# duinolpcfwhspi.net
KiCad netlist of a schematic drawn in EAGLE
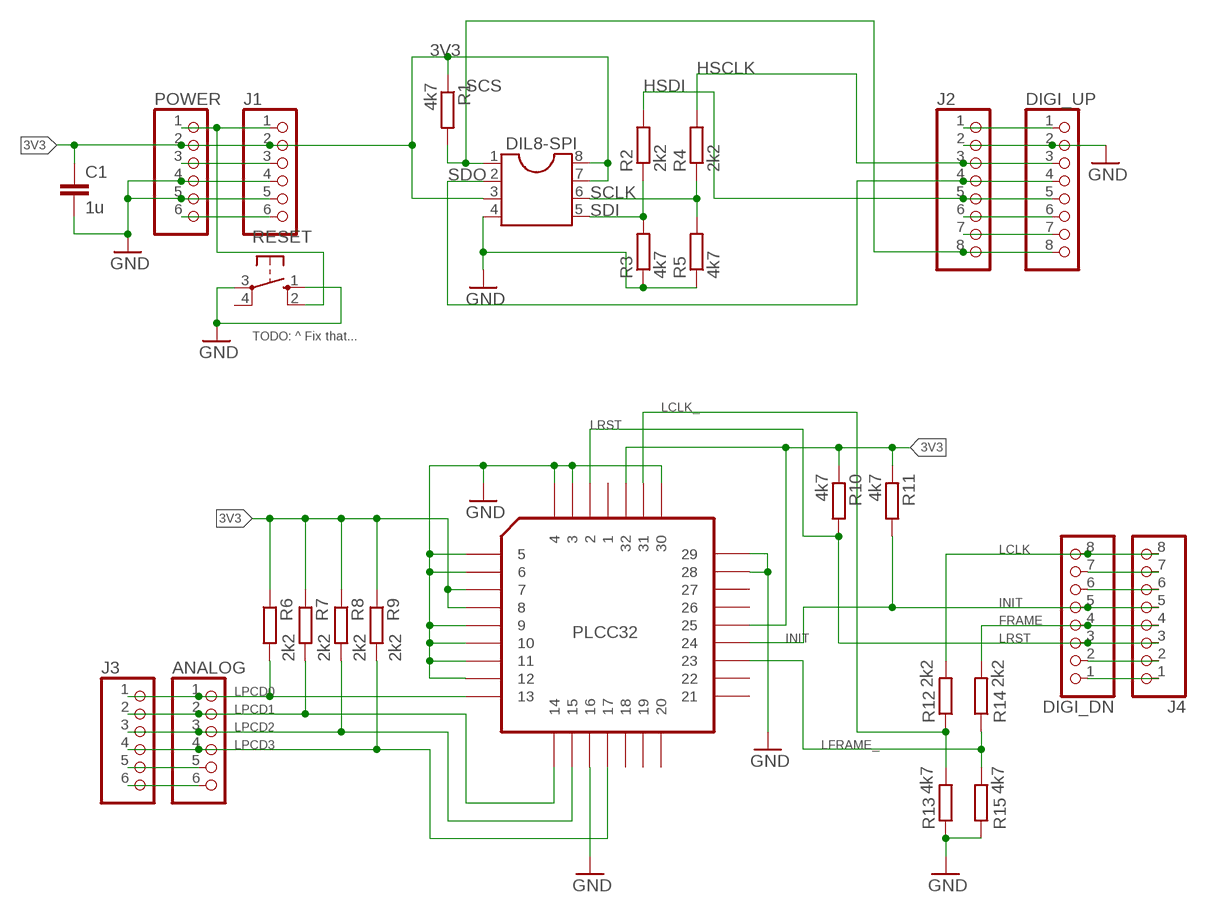
[diagram p0: schematic, sheet 1]

(export (version "E")
  (design (tool "Eeschema 10.0.6"))
  (components
    (comp (ref "ANALOG")
      (value "PINHD-1X6")
      (footprint "eagle-import:1X06")
      (libsource (lib "eagle-import") (part "PINHD-1X6"))
    )
    (comp (ref "C1")
      (value "1u")
      (footprint "eagle-import:C025-025X050")
      (libsource (lib "eagle-import") (part "C-EU025-025X050"))
    )
    (comp (ref "DIGI_DN")
      (value "PINHD-1X8TH")
      (footprint "eagle-import:1X08-TH")
      (libsource (lib "eagle-import") (part "PINHD-1X8TH"))
    )
    (comp (ref "DIGI_UP")
      (value "PINHD-1X8TH")
      (footprint "eagle-import:1X08-TH")
      (libsource (lib "eagle-import") (part "PINHD-1X8TH"))
    )
    (comp (ref "DIL8-SPI")
      (value "DIL8")
      (footprint "eagle-import:DIL08")
      (libsource (lib "eagle-import") (part "DIL8"))
    )
    (comp (ref "J1")
      (value "PINHD-1X6")
      (footprint "eagle-import:1X06")
      (libsource (lib "eagle-import") (part "PINHD-1X6"))
    )
    (comp (ref "J2")
      (value "PINHD-1X8TH")
      (footprint "eagle-import:1X08-TH")
      (libsource (lib "eagle-import") (part "PINHD-1X8TH"))
    )
    (comp (ref "J3")
      (value "PINHD-1X6")
      (footprint "eagle-import:1X06")
      (libsource (lib "eagle-import") (part "PINHD-1X6"))
    )
    (comp (ref "J4")
      (value "PINHD-1X8TH")
      (footprint "eagle-import:1X08-TH")
      (libsource (lib "eagle-import") (part "PINHD-1X8TH"))
    )
    (comp (ref "PLCC32")
      (value "PLCC32")
      (footprint "eagle-import:PLCC-S32")
      (libsource (lib "eagle-import") (part "PLCC32"))
    )
    (comp (ref "POWER")
      (value "PINHD-1X6")
      (footprint "eagle-import:1X06")
      (libsource (lib "eagle-import") (part "PINHD-1X6"))
    )
    (comp (ref "R1")
      (value "4k7")
      (footprint "eagle-import:0207_2V")
      (libsource (lib "eagle-import") (part "R-EU_0207/2V"))
    )
    (comp (ref "R2")
      (value "2k2")
      (footprint "eagle-import:0207_2V")
      (libsource (lib "eagle-import") (part "R-EU_0207/2V"))
    )
    (comp (ref "R3")
      (value "4k7")
      (footprint "eagle-import:0207_2V")
      (libsource (lib "eagle-import") (part "R-EU_0207/2V"))
    )
    (comp (ref "R4")
      (value "2k2")
      (footprint "eagle-import:0207_2V")
      (libsource (lib "eagle-import") (part "R-EU_0207/2V"))
    )
    (comp (ref "R5")
      (value "4k7")
      (footprint "eagle-import:0207_2V")
      (libsource (lib "eagle-import") (part "R-EU_0207/2V"))
    )
    (comp (ref "R6")
      (value "2k2")
      (footprint "eagle-import:0207_2V")
      (libsource (lib "eagle-import") (part "R-EU_0207/2V"))
    )
    (comp (ref "R7")
      (value "2k2")
      (footprint "eagle-import:0207_2V")
      (libsource (lib "eagle-import") (part "R-EU_0207/2V"))
    )
    (comp (ref "R8")
      (value "2k2")
      (footprint "eagle-import:0207_2V")
      (libsource (lib "eagle-import") (part "R-EU_0207/2V"))
    )
    (comp (ref "R9")
      (value "2k2")
      (footprint "eagle-import:0207_2V")
      (libsource (lib "eagle-import") (part "R-EU_0207/2V"))
    )
    (comp (ref "R10")
      (value "4k7")
      (footprint "eagle-import:0207_2V")
      (libsource (lib "eagle-import") (part "R-EU_0207/2V"))
    )
    (comp (ref "R11")
      (value "4k7")
      (footprint "eagle-import:0207_2V")
      (libsource (lib "eagle-import") (part "R-EU_0207/2V"))
    )
    (comp (ref "R12")
      (value "2k2")
      (footprint "eagle-import:0207_2V")
      (libsource (lib "eagle-import") (part "R-EU_0207/2V"))
    )
    (comp (ref "R13")
      (value "4k7")
      (footprint "eagle-import:0207_2V")
      (libsource (lib "eagle-import") (part "R-EU_0207/2V"))
    )
    (comp (ref "R14")
      (value "2k2")
      (footprint "eagle-import:0207_2V")
      (libsource (lib "eagle-import") (part "R-EU_0207/2V"))
    )
    (comp (ref "R15")
      (value "4k7")
      (footprint "eagle-import:0207_2V")
      (libsource (lib "eagle-import") (part "R-EU_0207/2V"))
    )
    (comp (ref "RESET")
      (value "10-XX")
      (footprint "eagle-import:B3F-10XX")
      (libsource (lib "eagle-import") (part "10-XX"))
    )
  )
  (nets
    (net (code "1") (name "/FRAME") (class "Default")
      (node (ref "DIGI_DN") (pin "4") (pinfunction "4_4") (pintype "passive"))
      (node (ref "J4") (pin "4") (pinfunction "4_4") (pintype "passive"))
      (node (ref "R14") (pin "2") (pinfunction "2_2") (pintype "passive"))
    )
    (net (code "2") (name "/HSCLK") (class "Default")
      (node (ref "DIGI_UP") (pin "3") (pinfunction "3_3") (pintype "passive"))
      (node (ref "J2") (pin "3") (pinfunction "3_3") (pintype "passive"))
      (node (ref "R4") (pin "2") (pinfunction "2_2") (pintype "passive"))
    )
    (net (code "3") (name "/HSDI") (class "Default")
      (node (ref "DIGI_UP") (pin "5") (pinfunction "5_5") (pintype "passive"))
      (node (ref "J2") (pin "5") (pinfunction "5_5") (pintype "passive"))
      (node (ref "R2") (pin "2") (pinfunction "2_2") (pintype "passive"))
    )
    (net (code "4") (name "/INIT") (class "Default")
      (node (ref "DIGI_DN") (pin "5") (pinfunction "5_5") (pintype "passive"))
      (node (ref "J4") (pin "5") (pinfunction "5_5") (pintype "passive"))
      (node (ref "PLCC32") (pin "24") (pinfunction "24_24") (pintype "passive"))
      (node (ref "R11") (pin "2") (pinfunction "2_2") (pintype "passive"))
    )
    (net (code "5") (name "/LCLK") (class "Default")
      (node (ref "DIGI_DN") (pin "8") (pinfunction "8_8") (pintype "passive"))
      (node (ref "J4") (pin "8") (pinfunction "8_8") (pintype "passive"))
      (node (ref "R12") (pin "2") (pinfunction "2_2") (pintype "passive"))
    )
    (net (code "6") (name "/LCLK_") (class "Default")
      (node (ref "PLCC32") (pin "31") (pinfunction "31_31") (pintype "passive"))
      (node (ref "R12") (pin "1") (pinfunction "1_1") (pintype "passive"))
      (node (ref "R13") (pin "2") (pinfunction "2_2") (pintype "passive"))
    )
    (net (code "7") (name "/LFRAME_") (class "Default")
      (node (ref "PLCC32") (pin "23") (pinfunction "23_23") (pintype "passive"))
      (node (ref "R14") (pin "1") (pinfunction "1_1") (pintype "passive"))
      (node (ref "R15") (pin "2") (pinfunction "2_2") (pintype "passive"))
    )
    (net (code "8") (name "/LPCD0") (class "Default")
      (node (ref "ANALOG") (pin "1") (pinfunction "1_1") (pintype "passive"))
      (node (ref "J3") (pin "1") (pinfunction "1_1") (pintype "passive"))
      (node (ref "PLCC32") (pin "13") (pinfunction "13_13") (pintype "passive"))
      (node (ref "R6") (pin "2") (pinfunction "2_2") (pintype "passive"))
    )
    (net (code "9") (name "/LPCD1") (class "Default")
      (node (ref "ANALOG") (pin "2") (pinfunction "2_2") (pintype "passive"))
      (node (ref "J3") (pin "2") (pinfunction "2_2") (pintype "passive"))
      (node (ref "PLCC32") (pin "14") (pinfunction "14_14") (pintype "passive"))
      (node (ref "R7") (pin "2") (pinfunction "2_2") (pintype "passive"))
    )
    (net (code "10") (name "/LPCD2") (class "Default")
      (node (ref "ANALOG") (pin "3") (pinfunction "3_3") (pintype "passive"))
      (node (ref "J3") (pin "3") (pinfunction "3_3") (pintype "passive"))
      (node (ref "PLCC32") (pin "15") (pinfunction "15_15") (pintype "passive"))
      (node (ref "R8") (pin "2") (pinfunction "2_2") (pintype "passive"))
    )
    (net (code "11") (name "/LPCD3") (class "Default")
      (node (ref "ANALOG") (pin "4") (pinfunction "4_4") (pintype "passive"))
      (node (ref "J3") (pin "4") (pinfunction "4_4") (pintype "passive"))
      (node (ref "PLCC32") (pin "17") (pinfunction "17_17") (pintype "passive"))
      (node (ref "R9") (pin "2") (pinfunction "2_2") (pintype "passive"))
    )
    (net (code "12") (name "/LRST") (class "Default")
      (node (ref "DIGI_DN") (pin "3") (pinfunction "3_3") (pintype "passive"))
      (node (ref "J4") (pin "3") (pinfunction "3_3") (pintype "passive"))
      (node (ref "PLCC32") (pin "2") (pinfunction "2_2") (pintype "passive"))
      (node (ref "R10") (pin "2") (pinfunction "2_2") (pintype "passive"))
    )
    (net (code "13") (name "/SCLK") (class "Default")
      (node (ref "DIL8-SPI") (pin "6") (pinfunction "6_6") (pintype "passive"))
      (node (ref "R4") (pin "1") (pinfunction "1_1") (pintype "passive"))
      (node (ref "R5") (pin "2") (pinfunction "2_2") (pintype "passive"))
    )
    (net (code "14") (name "/SCS") (class "Default")
      (node (ref "DIGI_UP") (pin "8") (pinfunction "8_8") (pintype "passive"))
      (node (ref "DIL8-SPI") (pin "1") (pinfunction "1_1") (pintype "passive"))
      (node (ref "J2") (pin "8") (pinfunction "8_8") (pintype "passive"))
      (node (ref "R1") (pin "2") (pinfunction "2_2") (pintype "passive"))
    )
    (net (code "15") (name "/SDI") (class "Default")
      (node (ref "DIL8-SPI") (pin "5") (pinfunction "5_5") (pintype "passive"))
      (node (ref "R2") (pin "1") (pinfunction "1_1") (pintype "passive"))
      (node (ref "R3") (pin "2") (pinfunction "2_2") (pintype "passive"))
    )
    (net (code "16") (name "/SDO") (class "Default")
      (node (ref "DIGI_UP") (pin "4") (pinfunction "4_4") (pintype "passive"))
      (node (ref "DIL8-SPI") (pin "2") (pinfunction "2_2") (pintype "passive"))
      (node (ref "J2") (pin "4") (pinfunction "4_4") (pintype "passive"))
    )
    (net (code "17") (name "3V3") (class "Default")
      (node (ref "C1") (pin "1") (pinfunction "1_1") (pintype "passive"))
      (node (ref "DIL8-SPI") (pin "3") (pinfunction "3_3") (pintype "passive"))
      (node (ref "DIL8-SPI") (pin "7") (pinfunction "7_7") (pintype "passive"))
      (node (ref "DIL8-SPI") (pin "8") (pinfunction "8_8") (pintype "passive"))
      (node (ref "J1") (pin "2") (pinfunction "2_2") (pintype "passive"))
      (node (ref "PLCC32") (pin "25") (pinfunction "25_25") (pintype "passive"))
      (node (ref "PLCC32") (pin "32") (pinfunction "32_32") (pintype "passive"))
      (node (ref "PLCC32") (pin "7") (pinfunction "7_7") (pintype "passive"))
      (node (ref "PLCC32") (pin "8") (pinfunction "8_8") (pintype "passive"))
      (node (ref "POWER") (pin "2") (pinfunction "2_2") (pintype "passive"))
      (node (ref "R1") (pin "1") (pinfunction "1_1") (pintype "passive"))
      (node (ref "R10") (pin "1") (pinfunction "1_1") (pintype "passive"))
      (node (ref "R11") (pin "1") (pinfunction "1_1") (pintype "passive"))
      (node (ref "R6") (pin "1") (pinfunction "1_1") (pintype "passive"))
      (node (ref "R7") (pin "1") (pinfunction "1_1") (pintype "passive"))
      (node (ref "R8") (pin "1") (pinfunction "1_1") (pintype "passive"))
      (node (ref "R9") (pin "1") (pinfunction "1_1") (pintype "passive"))
    )
    (net (code "18") (name "GND") (class "Default")
      (node (ref "C1") (pin "2") (pinfunction "2_2") (pintype "passive"))
      (node (ref "DIGI_UP") (pin "2") (pinfunction "2_2") (pintype "passive"))
      (node (ref "DIL8-SPI") (pin "4") (pinfunction "4_4") (pintype "passive"))
      (node (ref "J1") (pin "4") (pinfunction "4_4") (pintype "passive"))
      (node (ref "J1") (pin "5") (pinfunction "5_5") (pintype "passive"))
      (node (ref "J2") (pin "2") (pinfunction "2_2") (pintype "passive"))
      (node (ref "PLCC32") (pin "10") (pinfunction "10_10") (pintype "passive"))
      (node (ref "PLCC32") (pin "11") (pinfunction "11_11") (pintype "passive"))
      (node (ref "PLCC32") (pin "12") (pinfunction "12_12") (pintype "passive"))
      (node (ref "PLCC32") (pin "16") (pinfunction "16_16") (pintype "passive"))
      (node (ref "PLCC32") (pin "28") (pinfunction "28_28") (pintype "passive"))
      (node (ref "PLCC32") (pin "29") (pinfunction "29_29") (pintype "passive"))
      (node (ref "PLCC32") (pin "3") (pinfunction "3_3") (pintype "passive"))
      (node (ref "PLCC32") (pin "30") (pinfunction "30_30") (pintype "passive"))
      (node (ref "PLCC32") (pin "4") (pinfunction "4_4") (pintype "passive"))
      (node (ref "PLCC32") (pin "5") (pinfunction "5_5") (pintype "passive"))
      (node (ref "PLCC32") (pin "6") (pinfunction "6_6") (pintype "passive"))
      (node (ref "PLCC32") (pin "9") (pinfunction "9_9") (pintype "passive"))
      (node (ref "POWER") (pin "4") (pinfunction "4_4") (pintype "passive"))
      (node (ref "POWER") (pin "5") (pinfunction "5_5") (pintype "passive"))
      (node (ref "R13") (pin "1") (pinfunction "1_1") (pintype "passive"))
      (node (ref "R15") (pin "1") (pinfunction "1_1") (pintype "passive"))
      (node (ref "R3") (pin "1") (pinfunction "1_1") (pintype "passive"))
      (node (ref "R5") (pin "1") (pinfunction "1_1") (pintype "passive"))
      (node (ref "RESET") (pin "1") (pinfunction "S_1") (pintype "passive"))
      (node (ref "RESET") (pin "3") (pinfunction "P_3") (pintype "passive"))
    )
    (net (code "19") (name "Net-(ANALOG-Pad5)") (class "Default")
      (node (ref "ANALOG") (pin "5") (pinfunction "5_5") (pintype "passive"))
      (node (ref "J3") (pin "5") (pinfunction "5_5") (pintype "passive"))
    )
    (net (code "20") (name "Net-(ANALOG-Pad6)") (class "Default")
      (node (ref "ANALOG") (pin "6") (pinfunction "6_6") (pintype "passive"))
      (node (ref "J3") (pin "6") (pinfunction "6_6") (pintype "passive"))
    )
    (net (code "21") (name "Net-(DIGI_DN-Pad1)") (class "Default")
      (node (ref "DIGI_DN") (pin "1") (pinfunction "1_1") (pintype "passive"))
      (node (ref "J4") (pin "1") (pinfunction "1_1") (pintype "passive"))
    )
    (net (code "22") (name "Net-(DIGI_DN-Pad2)") (class "Default")
      (node (ref "DIGI_DN") (pin "2") (pinfunction "2_2") (pintype "passive"))
      (node (ref "J4") (pin "2") (pinfunction "2_2") (pintype "passive"))
    )
    (net (code "23") (name "Net-(DIGI_DN-Pad6)") (class "Default")
      (node (ref "DIGI_DN") (pin "6") (pinfunction "6_6") (pintype "passive"))
      (node (ref "J4") (pin "6") (pinfunction "6_6") (pintype "passive"))
    )
    (net (code "24") (name "Net-(DIGI_DN-Pad7)") (class "Default")
      (node (ref "DIGI_DN") (pin "7") (pinfunction "7_7") (pintype "passive"))
      (node (ref "J4") (pin "7") (pinfunction "7_7") (pintype "passive"))
    )
    (net (code "25") (name "Net-(DIGI_UP-Pad1)") (class "Default")
      (node (ref "DIGI_UP") (pin "1") (pinfunction "1_1") (pintype "passive"))
      (node (ref "J2") (pin "1") (pinfunction "1_1") (pintype "passive"))
    )
    (net (code "26") (name "Net-(DIGI_UP-Pad6)") (class "Default")
      (node (ref "DIGI_UP") (pin "6") (pinfunction "6_6") (pintype "passive"))
      (node (ref "J2") (pin "6") (pinfunction "6_6") (pintype "passive"))
    )
    (net (code "27") (name "Net-(DIGI_UP-Pad7)") (class "Default")
      (node (ref "DIGI_UP") (pin "7") (pinfunction "7_7") (pintype "passive"))
      (node (ref "J2") (pin "7") (pinfunction "7_7") (pintype "passive"))
    )
    (net (code "28") (name "Net-(J1-Pad3)") (class "Default")
      (node (ref "J1") (pin "3") (pinfunction "3_3") (pintype "passive"))
      (node (ref "POWER") (pin "3") (pinfunction "3_3") (pintype "passive"))
    )
    (net (code "29") (name "Net-(J1-Pad6)") (class "Default")
      (node (ref "J1") (pin "6") (pinfunction "6_6") (pintype "passive"))
      (node (ref "POWER") (pin "6") (pinfunction "6_6") (pintype "passive"))
    )
    (net (code "30") (name "Net-(RESET-S1)") (class "Default")
      (node (ref "J1") (pin "1") (pinfunction "1_1") (pintype "passive"))
      (node (ref "POWER") (pin "1") (pinfunction "1_1") (pintype "passive"))
      (node (ref "RESET") (pin "2") (pinfunction "S1_2") (pintype "passive"))
    )
    (net (code "31") (name "unconnected-(PLCC32-Pad1)") (class "Default")
      (node (ref "PLCC32") (pin "1") (pinfunction "1_1") (pintype "passive"))
    )
    (net (code "32") (name "unconnected-(PLCC32-Pad18)") (class "Default")
      (node (ref "PLCC32") (pin "18") (pinfunction "18_18") (pintype "passive"))
    )
    (net (code "33") (name "unconnected-(PLCC32-Pad19)") (class "Default")
      (node (ref "PLCC32") (pin "19") (pinfunction "19_19") (pintype "passive"))
    )
    (net (code "34") (name "unconnected-(PLCC32-Pad20)") (class "Default")
      (node (ref "PLCC32") (pin "20") (pinfunction "20_20") (pintype "passive"))
    )
    (net (code "35") (name "unconnected-(PLCC32-Pad21)") (class "Default")
      (node (ref "PLCC32") (pin "21") (pinfunction "21_21") (pintype "passive"))
    )
    (net (code "36") (name "unconnected-(PLCC32-Pad22)") (class "Default")
      (node (ref "PLCC32") (pin "22") (pinfunction "22_22") (pintype "passive"))
    )
    (net (code "37") (name "unconnected-(PLCC32-Pad26)") (class "Default")
      (node (ref "PLCC32") (pin "26") (pinfunction "26_26") (pintype "passive"))
    )
    (net (code "38") (name "unconnected-(PLCC32-Pad27)") (class "Default")
      (node (ref "PLCC32") (pin "27") (pinfunction "27_27") (pintype "passive"))
    )
    (net (code "39") (name "unconnected-(RESET-P1-Pad4)") (class "Default")
      (node (ref "RESET") (pin "4") (pinfunction "P1_4") (pintype "passive"))
    )
  )
)
